# bleumaus-nrf51822-mk-2_0_0.net
KiCad netlist of a schematic drawn in EAGLE
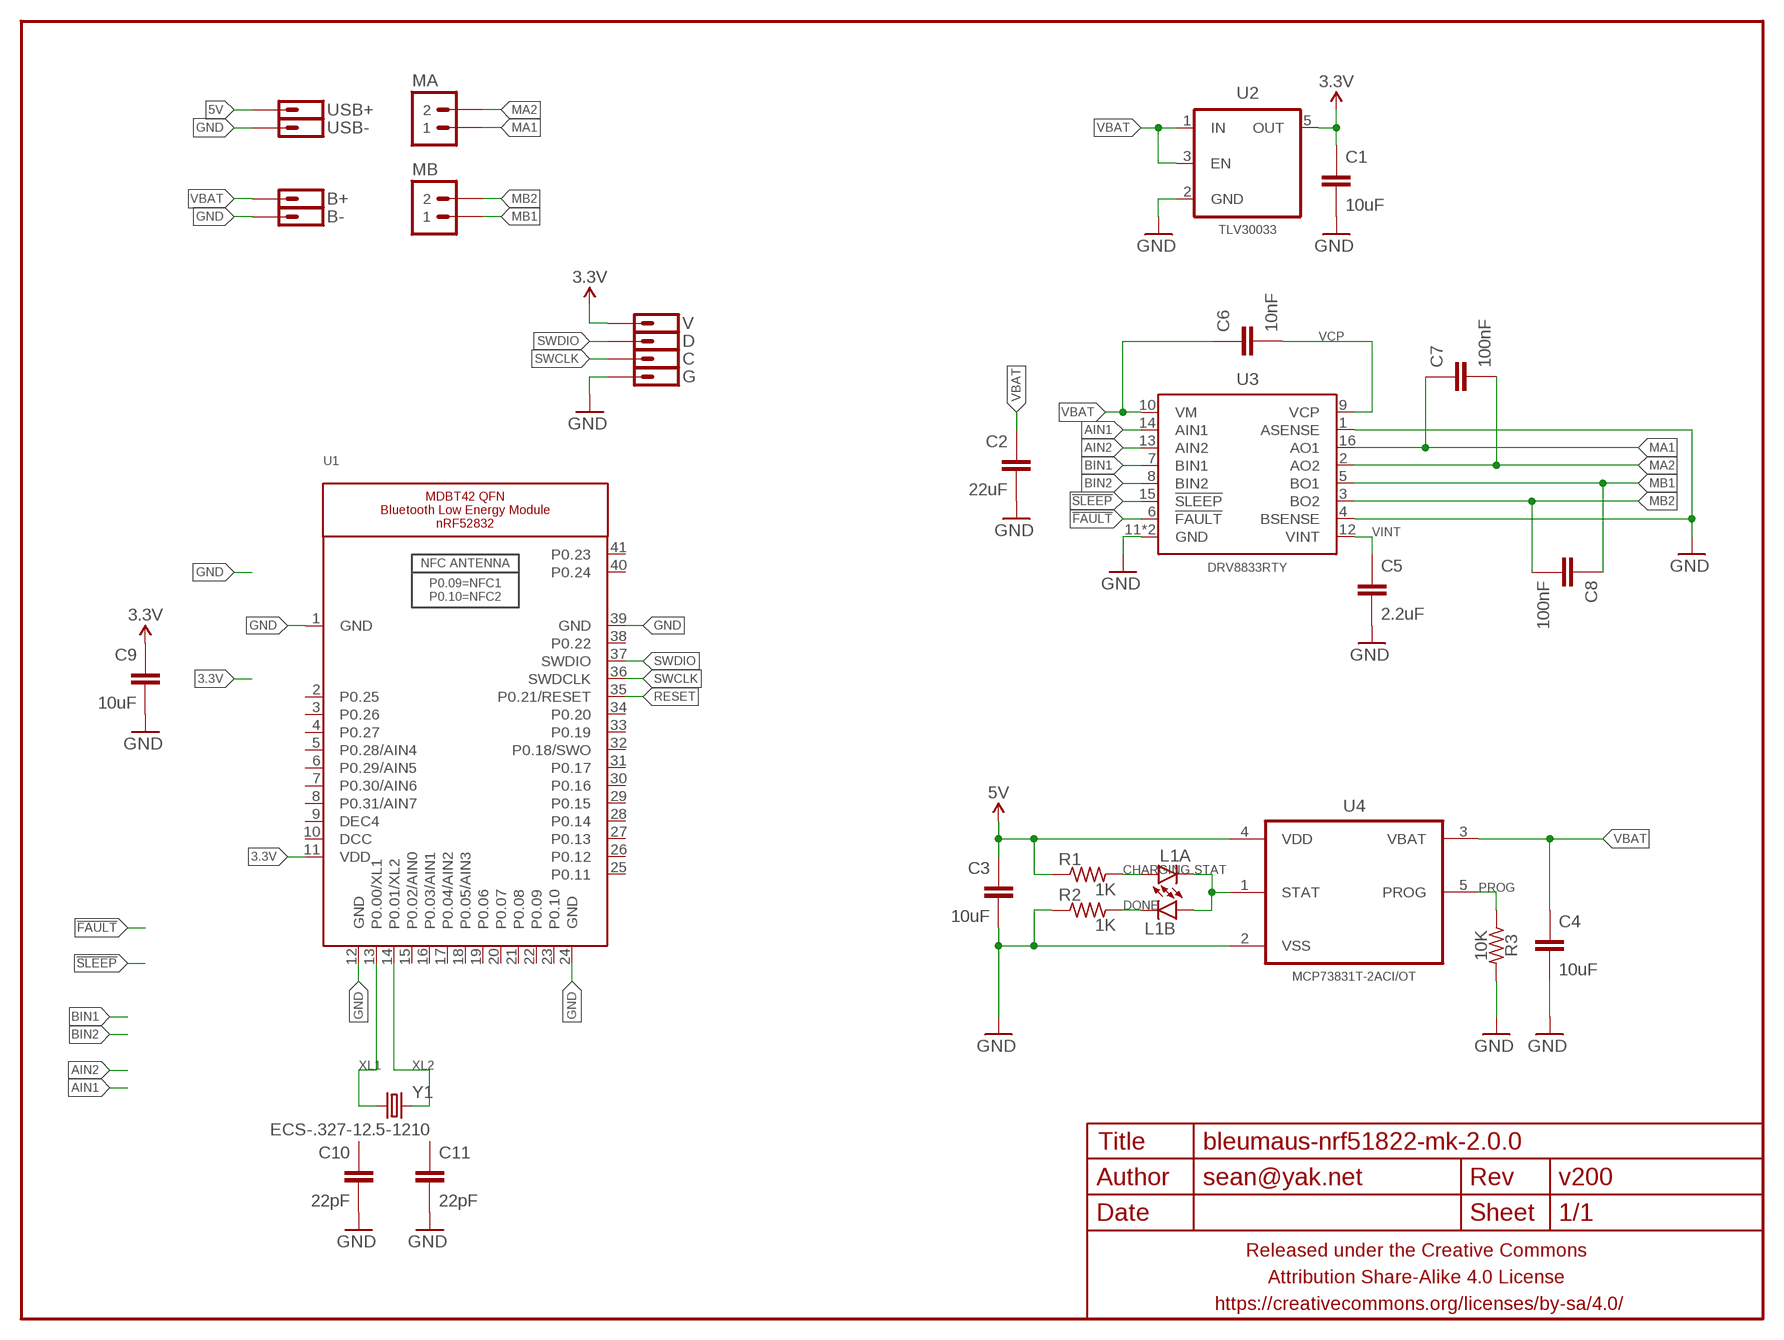
[diagram p0: schematic, sheet 1]

(export (version "E")
  (design (tool "Eeschema 10.0.6"))
  (components
    (comp (ref "B+")
      (value "M01SMD-1DIA")
      (footprint "eagle-import:1X01-SMD-1MM-DIA")
      (libsource (lib "eagle-import") (part "M01SMD-1DIA"))
    )
    (comp (ref "B-")
      (value "M01SMD-1DIA")
      (footprint "eagle-import:1X01-SMD-1MM-DIA")
      (libsource (lib "eagle-import") (part "M01SMD-1DIA"))
    )
    (comp (ref "C")
      (value "M01SMD-1DIA")
      (footprint "eagle-import:1X01-SMD-1MM-DIA")
      (libsource (lib "eagle-import") (part "M01SMD-1DIA"))
    )
    (comp (ref "C1")
      (value "10uF")
      (footprint "eagle-import:C0402")
      (libsource (lib "eagle-import") (part "CAPACITOR-CERAMICC0402"))
    )
    (comp (ref "C2")
      (value "22uF")
      (footprint "eagle-import:C1206")
      (libsource (lib "eagle-import") (part "CAPACITOR-CERAMICC1206"))
    )
    (comp (ref "C3")
      (value "10uF")
      (footprint "eagle-import:C0402")
      (libsource (lib "eagle-import") (part "CAPACITOR-CERAMICC0402"))
    )
    (comp (ref "C4")
      (value "10uF")
      (footprint "eagle-import:C0402")
      (libsource (lib "eagle-import") (part "CAPACITOR-CERAMICC0402"))
    )
    (comp (ref "C5")
      (value "2.2uF")
      (footprint "eagle-import:C0402")
      (libsource (lib "eagle-import") (part "CAPACITOR-CERAMICC0402"))
    )
    (comp (ref "C6")
      (value "10nF")
      (footprint "eagle-import:C0402")
      (libsource (lib "eagle-import") (part "CAPACITOR-CERAMICC0402"))
    )
    (comp (ref "C7")
      (value "100nF")
      (footprint "eagle-import:C0402")
      (libsource (lib "eagle-import") (part "CAPACITOR-CERAMICC0402"))
    )
    (comp (ref "C8")
      (value "100nF")
      (footprint "eagle-import:C0402")
      (libsource (lib "eagle-import") (part "CAPACITOR-CERAMICC0402"))
    )
    (comp (ref "C9")
      (value "10uF")
      (footprint "eagle-import:C0402")
      (libsource (lib "eagle-import") (part "CAPACITOR-CERAMICC0402"))
    )
    (comp (ref "C10")
      (value "22pF")
      (footprint "eagle-import:C0402")
      (libsource (lib "eagle-import") (part "CAPACITOR-CERAMICC0402"))
    )
    (comp (ref "C11")
      (value "22pF")
      (footprint "eagle-import:C0402")
      (libsource (lib "eagle-import") (part "CAPACITOR-CERAMICC0402"))
    )
    (comp (ref "D")
      (value "M01SMD-1DIA")
      (footprint "eagle-import:1X01-SMD-1MM-DIA")
      (libsource (lib "eagle-import") (part "M01SMD-1DIA"))
    )
    (comp (ref "FRAME1")
      (value "FRAME-LETTERNO_PACKAGE")
      (footprint "eagle-import:DUMMY")
      (fields
        (field (name "DESIGNER") "sean@yak.net")
        (field (name "VERSION") "v200")
        (field (name "DESIGNER_1") "sean@yak.net")
        (field (name "VERSION_1") "v200")
      )
      (libsource (lib "eagle-import") (part "FRAME-LETTERNO_PACKAGE"))
    )
    (comp (ref "G")
      (value "M01SMD-1DIA")
      (footprint "eagle-import:1X01-SMD-1MM-DIA")
      (libsource (lib "eagle-import") (part "M01SMD-1DIA"))
    )
    (comp (ref "L1")
      (value "LED-BICOLORSML-P24MUW")
      (footprint "eagle-import:SML-P24MUW")
      (libsource (lib "eagle-import") (part "LED-BICOLORSML-P24MUW"))
    )
    (comp (ref "MA")
      (value "M02PTH-2MM")
      (footprint "eagle-import:1X02-2MM-PTH")
      (libsource (lib "eagle-import") (part "M02PTH-2MM"))
    )
    (comp (ref "MB")
      (value "M02PTH-2MM")
      (footprint "eagle-import:1X02-2MM-PTH")
      (libsource (lib "eagle-import") (part "M02PTH-2MM"))
    )
    (comp (ref "R1")
      (value "1K")
      (footprint "eagle-import:R0402")
      (libsource (lib "eagle-import") (part "RESISTORR0402"))
    )
    (comp (ref "R2")
      (value "1K")
      (footprint "eagle-import:R0402")
      (libsource (lib "eagle-import") (part "RESISTORR0402"))
    )
    (comp (ref "R3")
      (value "10K")
      (footprint "eagle-import:R0402")
      (libsource (lib "eagle-import") (part "RESISTORR0402"))
    )
    (comp (ref "U1")
      (value "NRF52832_MODULE_MDBT42")
      (footprint "eagle-import:BLE_MODULE_RAYTAC_MDBT42")
      (libsource (lib "eagle-import") (part "NRF52832_MODULE_MDBT42"))
    )
    (comp (ref "U2")
      (value "TLV30033")
      (footprint "eagle-import:SC70-TIGHTER")
      (libsource (lib "eagle-import") (part "V_REG_ENTLV700XXDCK-TIGHTER"))
    )
    (comp (ref "U3")
      (value "DRV8833RTY")
      (footprint "eagle-import:PWQFN-16")
      (libsource (lib "eagle-import") (part "DRV8833RTY"))
    )
    (comp (ref "U4")
      (value "MCP73831T-2ACI/OT")
      (footprint "eagle-import:SOT95P280X145-5N")
      (libsource (lib "eagle-import") (part "MCP73831T-2ACI/OT"))
    )
    (comp (ref "USB+")
      (value "M01SMD-1DIA")
      (footprint "eagle-import:1X01-SMD-1MM-DIA")
      (libsource (lib "eagle-import") (part "M01SMD-1DIA"))
    )
    (comp (ref "USB-")
      (value "M01SMD-1DIA")
      (footprint "eagle-import:1X01-SMD-1MM-DIA")
      (libsource (lib "eagle-import") (part "M01SMD-1DIA"))
    )
    (comp (ref "V")
      (value "M01SMD-1DIA")
      (footprint "eagle-import:1X01-SMD-1MM-DIA")
      (libsource (lib "eagle-import") (part "M01SMD-1DIA"))
    )
    (comp (ref "Y1")
      (value "ECS-.327-12.5-1210")
      (footprint "eagle-import:CRYSTAL-1X1.2MM")
      (libsource (lib "eagle-import") (part "CRYSTAL1X1.2MM"))
    )
  )
  (nets
    (net (code "1") (name "/CHARGING") (class "Default")
      (node (ref "L1") (pin "1") (pinfunction "A_1") (pintype "passive"))
      (node (ref "R1") (pin "2") (pinfunction "2_2") (pintype "passive"))
    )
    (net (code "2") (name "/DONE") (class "Default")
      (node (ref "L1") (pin "3") (pinfunction "C_3") (pintype "passive"))
      (node (ref "R2") (pin "2") (pinfunction "2_2") (pintype "passive"))
    )
    (net (code "3") (name "/PROG") (class "Default")
      (node (ref "R3") (pin "1") (pinfunction "1_1") (pintype "passive"))
      (node (ref "U4") (pin "5") (pinfunction "PROG_5") (pintype "input"))
    )
    (net (code "4") (name "/STAT") (class "Default")
      (node (ref "L1") (pin "2") (pinfunction "A_2") (pintype "passive"))
      (node (ref "L1") (pin "4") (pinfunction "C_4") (pintype "passive"))
      (node (ref "U4") (pin "1") (pinfunction "STAT_1") (pintype "output"))
    )
    (net (code "5") (name "/VCP") (class "Default")
      (node (ref "C6") (pin "2") (pinfunction "2_2") (pintype "passive"))
      (node (ref "U3") (pin "9") (pinfunction "VCP_9") (pintype "bidirectional"))
    )
    (net (code "6") (name "/VINT") (class "Default")
      (node (ref "C5") (pin "1") (pinfunction "1_1") (pintype "passive"))
      (node (ref "U3") (pin "12") (pinfunction "VINT_12") (pintype "bidirectional"))
    )
    (net (code "7") (name "/XL1") (class "Default")
      (node (ref "U1") (pin "13") (pinfunction "P0.00/XL1_13") (pintype "bidirectional"))
      (node (ref "Y1") (pin "1") (pinfunction "1_1") (pintype "passive"))
    )
    (net (code "8") (name "/XL2") (class "Default")
      (node (ref "U1") (pin "14") (pinfunction "P0.01/XL2_14") (pintype "bidirectional"))
      (node (ref "Y1") (pin "2") (pinfunction "2_2") (pintype "passive"))
    )
    (net (code "9") (name "/~{FAULT}") (class "Default")
      (node (ref "U3") (pin "6") (pinfunction "~{FAULT}_6") (pintype "output"))
    )
    (net (code "10") (name "/~{SLEEP}") (class "Default")
      (node (ref "U3") (pin "15") (pinfunction "~{SLEEP}_15") (pintype "input"))
    )
    (net (code "11") (name "3.3V") (class "Default")
      (node (ref "C1") (pin "1") (pinfunction "1_1") (pintype "passive"))
      (node (ref "C9") (pin "1") (pinfunction "1_1") (pintype "passive"))
      (node (ref "U1") (pin "11") (pinfunction "VDD_11") (pintype "bidirectional"))
      (node (ref "U2") (pin "5") (pinfunction "OUT_5") (pintype "passive"))
      (node (ref "V") (pin "P$1") (pinfunction "1_P$1") (pintype "passive"))
    )
    (net (code "12") (name "5V") (class "Default")
      (node (ref "C3") (pin "1") (pinfunction "1_1") (pintype "passive"))
      (node (ref "R1") (pin "1") (pinfunction "1_1") (pintype "passive"))
      (node (ref "U4") (pin "4") (pinfunction "VDD_4") (pintype "power_in"))
      (node (ref "USB+") (pin "P$1") (pinfunction "1_P$1") (pintype "passive"))
    )
    (net (code "13") (name "AIN1") (class "Default")
      (node (ref "U3") (pin "14") (pinfunction "AIN1_14") (pintype "input"))
    )
    (net (code "14") (name "AIN2") (class "Default")
      (node (ref "U3") (pin "13") (pinfunction "AIN2_13") (pintype "input"))
    )
    (net (code "15") (name "BIN1") (class "Default")
      (node (ref "U3") (pin "7") (pinfunction "BIN1_7") (pintype "input"))
    )
    (net (code "16") (name "BIN2") (class "Default")
      (node (ref "U3") (pin "8") (pinfunction "BIN2_8") (pintype "input"))
    )
    (net (code "17") (name "GND") (class "Default")
      (node (ref "B-") (pin "P$1") (pinfunction "1_P$1") (pintype "passive"))
      (node (ref "C1") (pin "2") (pinfunction "2_2") (pintype "passive"))
      (node (ref "C10") (pin "2") (pinfunction "2_2") (pintype "passive"))
      (node (ref "C11") (pin "2") (pinfunction "2_2") (pintype "passive"))
      (node (ref "C2") (pin "2") (pinfunction "2_2") (pintype "passive"))
      (node (ref "C3") (pin "2") (pinfunction "2_2") (pintype "passive"))
      (node (ref "C4") (pin "2") (pinfunction "2_2") (pintype "passive"))
      (node (ref "C5") (pin "2") (pinfunction "2_2") (pintype "passive"))
      (node (ref "C9") (pin "2") (pinfunction "2_2") (pintype "passive"))
      (node (ref "G") (pin "P$1") (pinfunction "1_P$1") (pintype "passive"))
      (node (ref "R2") (pin "1") (pinfunction "1_1") (pintype "passive"))
      (node (ref "R3") (pin "2") (pinfunction "2_2") (pintype "passive"))
      (node (ref "U1") (pin "1") (pinfunction "GND_1") (pintype "bidirectional"))
      (node (ref "U1") (pin "12") (pinfunction "GND_12") (pintype "bidirectional"))
      (node (ref "U1") (pin "24") (pinfunction "GND_24") (pintype "bidirectional"))
      (node (ref "U1") (pin "39") (pinfunction "GND_39") (pintype "bidirectional"))
      (node (ref "U2") (pin "2") (pinfunction "GND_2") (pintype "input"))
      (node (ref "U3") (pin "1") (pinfunction "ASENSE_1") (pintype "bidirectional"))
      (node (ref "U3") (pin "11") (pinfunction "GND_11") (pintype "bidirectional"))
      (node (ref "U3") (pin "17") (pinfunction "GND_17") (pintype "bidirectional"))
      (node (ref "U3") (pin "4") (pinfunction "BSENSE_4") (pintype "bidirectional"))
      (node (ref "U4") (pin "2") (pinfunction "VSS_2") (pintype "power_in"))
      (node (ref "USB-") (pin "P$1") (pinfunction "1_P$1") (pintype "passive"))
    )
    (net (code "18") (name "MA1") (class "Default")
      (node (ref "C7") (pin "1") (pinfunction "1_1") (pintype "passive"))
      (node (ref "MA") (pin "P$1") (pinfunction "1_P$1") (pintype "passive"))
      (node (ref "U3") (pin "16") (pinfunction "AO1_16") (pintype "bidirectional"))
    )
    (net (code "19") (name "MA2") (class "Default")
      (node (ref "C7") (pin "2") (pinfunction "2_2") (pintype "passive"))
      (node (ref "MA") (pin "P$2") (pinfunction "2_P$2") (pintype "passive"))
      (node (ref "U3") (pin "2") (pinfunction "AO2_2") (pintype "bidirectional"))
    )
    (net (code "20") (name "MB1") (class "Default")
      (node (ref "C8") (pin "1") (pinfunction "1_1") (pintype "passive"))
      (node (ref "MB") (pin "P$1") (pinfunction "1_P$1") (pintype "passive"))
      (node (ref "U3") (pin "5") (pinfunction "BO1_5") (pintype "bidirectional"))
    )
    (net (code "21") (name "MB2") (class "Default")
      (node (ref "C8") (pin "2") (pinfunction "2_2") (pintype "passive"))
      (node (ref "MB") (pin "P$2") (pinfunction "2_P$2") (pintype "passive"))
      (node (ref "U3") (pin "3") (pinfunction "BO2_3") (pintype "bidirectional"))
    )
    (net (code "22") (name "RESET") (class "Default")
      (node (ref "U1") (pin "35") (pinfunction "P0.21/RESET_35") (pintype "bidirectional"))
    )
    (net (code "23") (name "SWCLK") (class "Default")
      (node (ref "C") (pin "P$1") (pinfunction "1_P$1") (pintype "passive"))
      (node (ref "U1") (pin "36") (pinfunction "SWDCLK_36") (pintype "bidirectional"))
    )
    (net (code "24") (name "SWDIO") (class "Default")
      (node (ref "D") (pin "P$1") (pinfunction "1_P$1") (pintype "passive"))
      (node (ref "U1") (pin "37") (pinfunction "SWDIO_37") (pintype "bidirectional"))
    )
    (net (code "25") (name "VBAT") (class "Default")
      (node (ref "B+") (pin "P$1") (pinfunction "1_P$1") (pintype "passive"))
      (node (ref "C2") (pin "1") (pinfunction "1_1") (pintype "passive"))
      (node (ref "C4") (pin "1") (pinfunction "1_1") (pintype "passive"))
      (node (ref "C6") (pin "1") (pinfunction "1_1") (pintype "passive"))
      (node (ref "U2") (pin "1") (pinfunction "IN_1") (pintype "input"))
      (node (ref "U2") (pin "3") (pinfunction "EN_3") (pintype "input"))
      (node (ref "U3") (pin "10") (pinfunction "VM_10") (pintype "bidirectional"))
      (node (ref "U4") (pin "3") (pinfunction "VBAT_3") (pintype "output"))
    )
    (net (code "26") (name "unconnected-(C10-Pad1)") (class "Default")
      (node (ref "C10") (pin "1") (pinfunction "1_1") (pintype "passive"))
    )
    (net (code "27") (name "unconnected-(C11-Pad1)") (class "Default")
      (node (ref "C11") (pin "1") (pinfunction "1_1") (pintype "passive"))
    )
    (net (code "28") (name "unconnected-(U1-DCC-Pad10)") (class "Default")
      (node (ref "U1") (pin "10") (pinfunction "DCC_10") (pintype "bidirectional"))
    )
    (net (code "29") (name "unconnected-(U1-DEC4-Pad9)") (class "Default")
      (node (ref "U1") (pin "9") (pinfunction "DEC4_9") (pintype "bidirectional"))
    )
    (net (code "30") (name "unconnected-(U1-P0.02{slash}AIN0-Pad15)") (class "Default")
      (node (ref "U1") (pin "15") (pinfunction "P0.02/AIN0_15") (pintype "bidirectional"))
    )
    (net (code "31") (name "unconnected-(U1-P0.03{slash}AIN1-Pad16)") (class "Default")
      (node (ref "U1") (pin "16") (pinfunction "P0.03/AIN1_16") (pintype "bidirectional"))
    )
    (net (code "32") (name "unconnected-(U1-P0.04{slash}AIN2-Pad17)") (class "Default")
      (node (ref "U1") (pin "17") (pinfunction "P0.04/AIN2_17") (pintype "bidirectional"))
    )
    (net (code "33") (name "unconnected-(U1-P0.05{slash}AIN3-Pad18)") (class "Default")
      (node (ref "U1") (pin "18") (pinfunction "P0.05/AIN3_18") (pintype "bidirectional"))
    )
    (net (code "34") (name "unconnected-(U1-P0.06-Pad19)") (class "Default")
      (node (ref "U1") (pin "19") (pinfunction "P0.06_19") (pintype "bidirectional"))
    )
    (net (code "35") (name "unconnected-(U1-P0.07-Pad20)") (class "Default")
      (node (ref "U1") (pin "20") (pinfunction "P0.07_20") (pintype "bidirectional"))
    )
    (net (code "36") (name "unconnected-(U1-P0.08-Pad21)") (class "Default")
      (node (ref "U1") (pin "21") (pinfunction "P0.08_21") (pintype "bidirectional"))
    )
    (net (code "37") (name "unconnected-(U1-P0.09-Pad22)") (class "Default")
      (node (ref "U1") (pin "22") (pinfunction "P0.09_22") (pintype "bidirectional"))
    )
    (net (code "38") (name "unconnected-(U1-P0.10-Pad23)") (class "Default")
      (node (ref "U1") (pin "23") (pinfunction "P0.10_23") (pintype "bidirectional"))
    )
    (net (code "39") (name "unconnected-(U1-P0.11-Pad25)") (class "Default")
      (node (ref "U1") (pin "25") (pinfunction "P0.11_25") (pintype "bidirectional"))
    )
    (net (code "40") (name "unconnected-(U1-P0.12-Pad26)") (class "Default")
      (node (ref "U1") (pin "26") (pinfunction "P0.12_26") (pintype "bidirectional"))
    )
    (net (code "41") (name "unconnected-(U1-P0.13-Pad27)") (class "Default")
      (node (ref "U1") (pin "27") (pinfunction "P0.13_27") (pintype "bidirectional"))
    )
    (net (code "42") (name "unconnected-(U1-P0.14-Pad28)") (class "Default")
      (node (ref "U1") (pin "28") (pinfunction "P0.14_28") (pintype "bidirectional"))
    )
    (net (code "43") (name "unconnected-(U1-P0.15-Pad29)") (class "Default")
      (node (ref "U1") (pin "29") (pinfunction "P0.15_29") (pintype "bidirectional"))
    )
    (net (code "44") (name "unconnected-(U1-P0.16-Pad30)") (class "Default")
      (node (ref "U1") (pin "30") (pinfunction "P0.16_30") (pintype "bidirectional"))
    )
    (net (code "45") (name "unconnected-(U1-P0.17-Pad31)") (class "Default")
      (node (ref "U1") (pin "31") (pinfunction "P0.17_31") (pintype "bidirectional"))
    )
    (net (code "46") (name "unconnected-(U1-P0.18{slash}SWO-Pad32)") (class "Default")
      (node (ref "U1") (pin "32") (pinfunction "P0.18/SWO_32") (pintype "bidirectional"))
    )
    (net (code "47") (name "unconnected-(U1-P0.19-Pad33)") (class "Default")
      (node (ref "U1") (pin "33") (pinfunction "P0.19_33") (pintype "bidirectional"))
    )
    (net (code "48") (name "unconnected-(U1-P0.20-Pad34)") (class "Default")
      (node (ref "U1") (pin "34") (pinfunction "P0.20_34") (pintype "bidirectional"))
    )
    (net (code "49") (name "unconnected-(U1-P0.22-Pad38)") (class "Default")
      (node (ref "U1") (pin "38") (pinfunction "P0.22_38") (pintype "bidirectional"))
    )
    (net (code "50") (name "unconnected-(U1-P0.23-Pad41)") (class "Default")
      (node (ref "U1") (pin "41") (pinfunction "P0.23_41") (pintype "bidirectional"))
    )
    (net (code "51") (name "unconnected-(U1-P0.24-Pad40)") (class "Default")
      (node (ref "U1") (pin "40") (pinfunction "P0.24_40") (pintype "bidirectional"))
    )
    (net (code "52") (name "unconnected-(U1-P0.25-Pad2)") (class "Default")
      (node (ref "U1") (pin "2") (pinfunction "P0.25_2") (pintype "bidirectional"))
    )
    (net (code "53") (name "unconnected-(U1-P0.26-Pad3)") (class "Default")
      (node (ref "U1") (pin "3") (pinfunction "P0.26_3") (pintype "bidirectional"))
    )
    (net (code "54") (name "unconnected-(U1-P0.27-Pad4)") (class "Default")
      (node (ref "U1") (pin "4") (pinfunction "P0.27_4") (pintype "bidirectional"))
    )
    (net (code "55") (name "unconnected-(U1-P0.28{slash}AIN4-Pad5)") (class "Default")
      (node (ref "U1") (pin "5") (pinfunction "P0.28/AIN4_5") (pintype "bidirectional"))
    )
    (net (code "56") (name "unconnected-(U1-P0.29{slash}AIN5-Pad6)") (class "Default")
      (node (ref "U1") (pin "6") (pinfunction "P0.29/AIN5_6") (pintype "bidirectional"))
    )
    (net (code "57") (name "unconnected-(U1-P0.30{slash}AIN6-Pad7)") (class "Default")
      (node (ref "U1") (pin "7") (pinfunction "P0.30/AIN6_7") (pintype "bidirectional"))
    )
    (net (code "58") (name "unconnected-(U1-P0.31{slash}AIN7-Pad8)") (class "Default")
      (node (ref "U1") (pin "8") (pinfunction "P0.31/AIN7_8") (pintype "bidirectional"))
    )
  )
)
